# LED_005.net
KiCad netlist of a schematic drawn in EAGLE
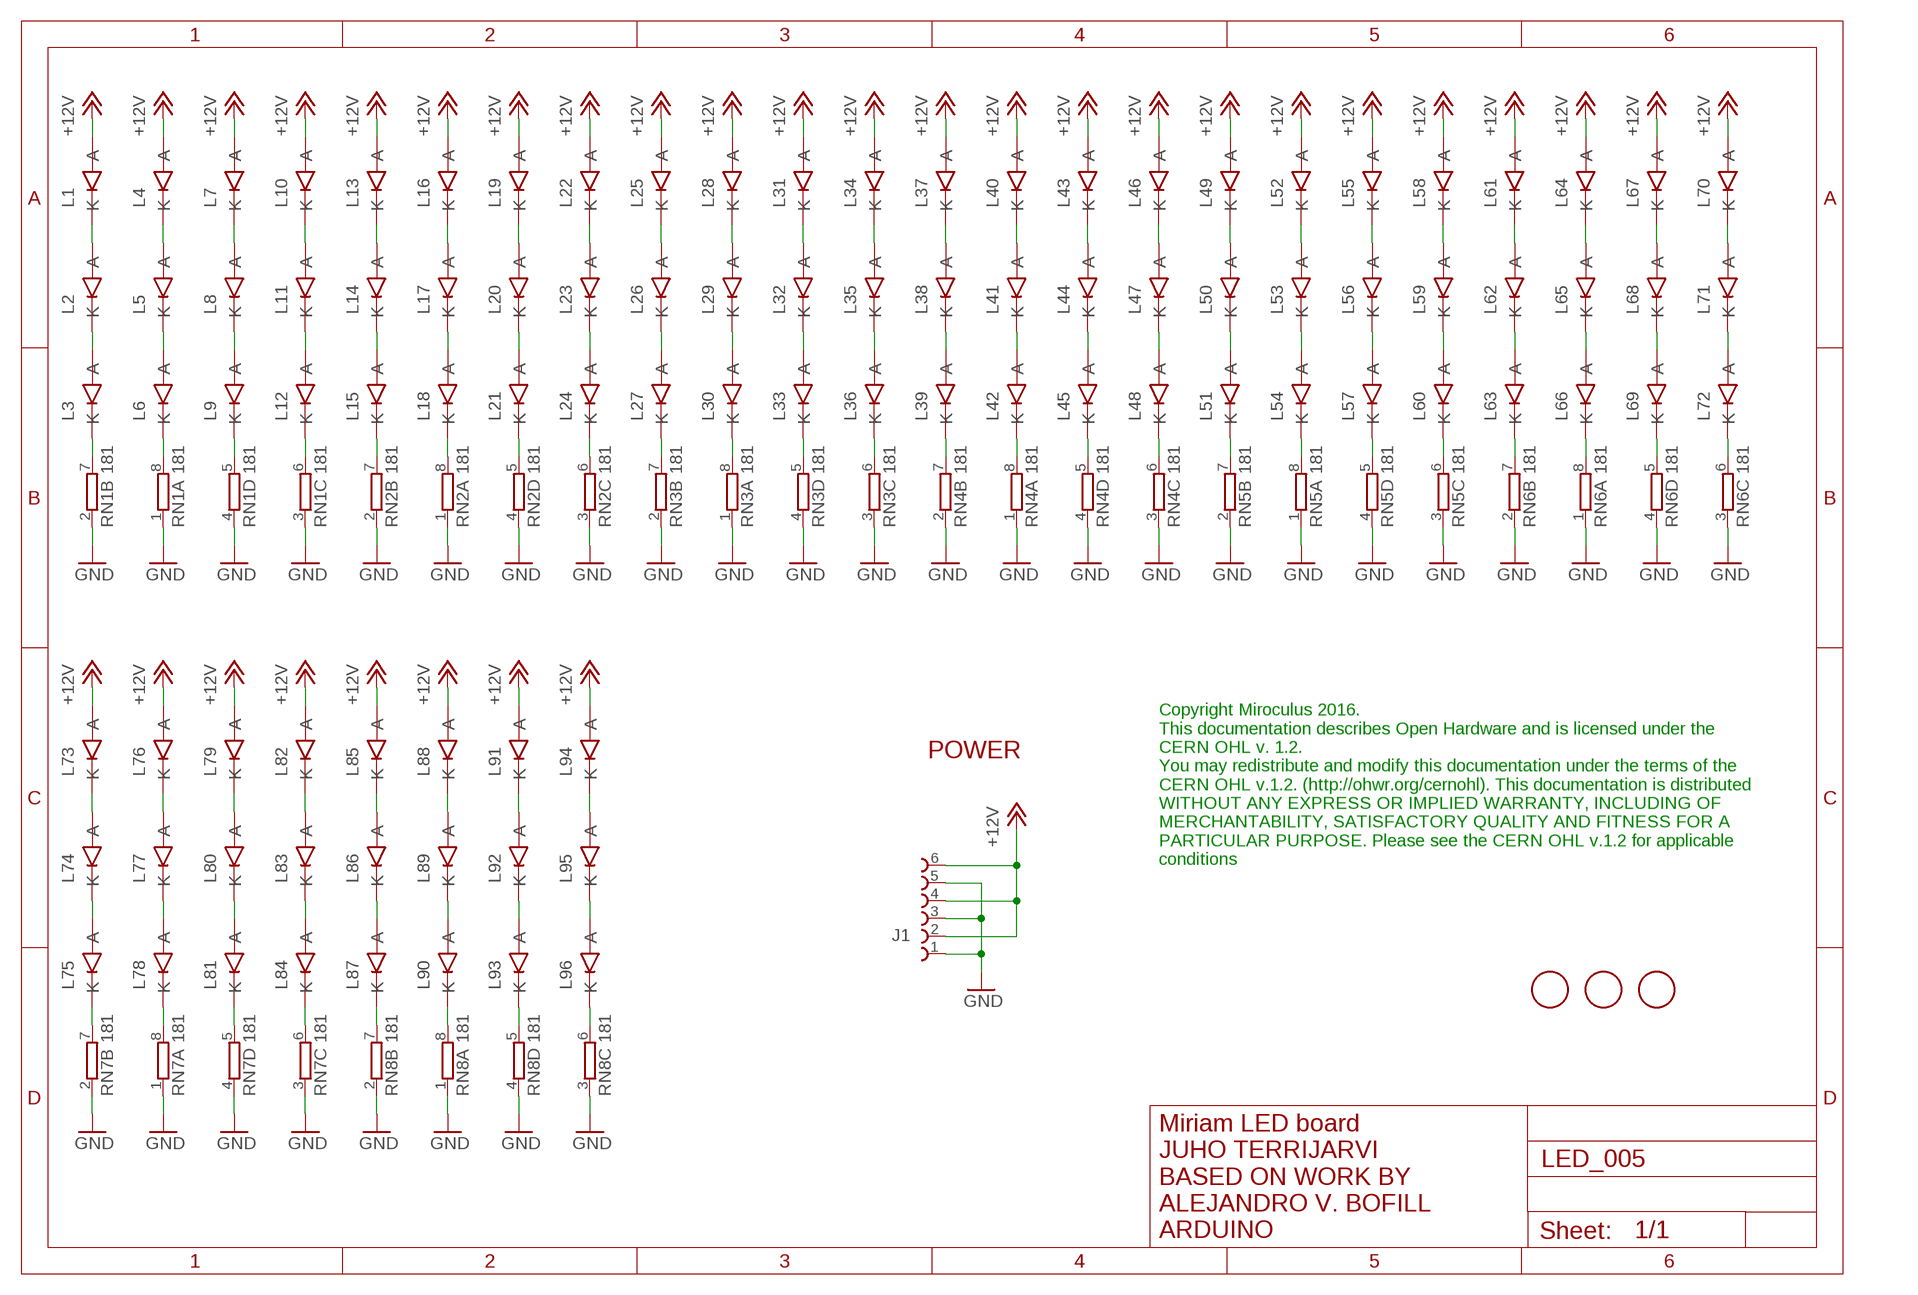
[diagram p0: schematic, sheet 1]

(export (version "E")
  (design (tool "Eeschema 10.0.6"))
  (components
    (comp (ref "FD1")
      (value "FIDUCIALMOUNT")
      (footprint "eagle-import:FIDUCIA-MOUNT")
      (libsource (lib "eagle-import") (part "FIDUCIALMOUNT"))
    )
    (comp (ref "FD2")
      (value "FIDUCIALMOUNT")
      (footprint "eagle-import:FIDUCIA-MOUNT")
      (libsource (lib "eagle-import") (part "FIDUCIALMOUNT"))
    )
    (comp (ref "FD3")
      (value "FIDUCIALMOUNT")
      (footprint "eagle-import:FIDUCIA-MOUNT")
      (libsource (lib "eagle-import") (part "FIDUCIALMOUNT"))
    )
    (comp (ref "J1")
      (value "68710614522")
      (footprint "eagle-import:68710614522")
      (libsource (lib "eagle-import") (part "68710614522"))
    )
    (comp (ref "L1")
      (value "KA-2810AQBS-G")
      (footprint "eagle-import:LED_0.2")
      (libsource (lib "eagle-import") (part "LED_0.2"))
    )
    (comp (ref "L2")
      (value "KA-2810AQBS-G")
      (footprint "eagle-import:LED_0.2")
      (libsource (lib "eagle-import") (part "LED_0.2"))
    )
    (comp (ref "L3")
      (value "KA-2810AQBS-G")
      (footprint "eagle-import:LED_0.2")
      (libsource (lib "eagle-import") (part "LED_0.2"))
    )
    (comp (ref "L4")
      (value "KA-2810AQBS-G")
      (footprint "eagle-import:LED_0.2")
      (libsource (lib "eagle-import") (part "LED_0.2"))
    )
    (comp (ref "L5")
      (value "KA-2810AQBS-G")
      (footprint "eagle-import:LED_0.2")
      (libsource (lib "eagle-import") (part "LED_0.2"))
    )
    (comp (ref "L6")
      (value "KA-2810AQBS-G")
      (footprint "eagle-import:LED_0.2")
      (libsource (lib "eagle-import") (part "LED_0.2"))
    )
    (comp (ref "L7")
      (value "KA-2810AQBS-G")
      (footprint "eagle-import:LED_0.2")
      (libsource (lib "eagle-import") (part "LED_0.2"))
    )
    (comp (ref "L8")
      (value "KA-2810AQBS-G")
      (footprint "eagle-import:LED_0.2")
      (libsource (lib "eagle-import") (part "LED_0.2"))
    )
    (comp (ref "L9")
      (value "KA-2810AQBS-G")
      (footprint "eagle-import:LED_0.2")
      (libsource (lib "eagle-import") (part "LED_0.2"))
    )
    (comp (ref "L10")
      (value "KA-2810AQBS-G")
      (footprint "eagle-import:LED_0.2")
      (libsource (lib "eagle-import") (part "LED_0.2"))
    )
    (comp (ref "L11")
      (value "KA-2810AQBS-G")
      (footprint "eagle-import:LED_0.2")
      (libsource (lib "eagle-import") (part "LED_0.2"))
    )
    (comp (ref "L12")
      (value "KA-2810AQBS-G")
      (footprint "eagle-import:LED_0.2")
      (libsource (lib "eagle-import") (part "LED_0.2"))
    )
    (comp (ref "L13")
      (value "KA-2810AQBS-G")
      (footprint "eagle-import:LED_0.2")
      (libsource (lib "eagle-import") (part "LED_0.2"))
    )
    (comp (ref "L14")
      (value "KA-2810AQBS-G")
      (footprint "eagle-import:LED_0.2")
      (libsource (lib "eagle-import") (part "LED_0.2"))
    )
    (comp (ref "L15")
      (value "KA-2810AQBS-G")
      (footprint "eagle-import:LED_0.2")
      (libsource (lib "eagle-import") (part "LED_0.2"))
    )
    (comp (ref "L16")
      (value "KA-2810AQBS-G")
      (footprint "eagle-import:LED_0.2")
      (libsource (lib "eagle-import") (part "LED_0.2"))
    )
    (comp (ref "L17")
      (value "KA-2810AQBS-G")
      (footprint "eagle-import:LED_0.2")
      (libsource (lib "eagle-import") (part "LED_0.2"))
    )
    (comp (ref "L18")
      (value "KA-2810AQBS-G")
      (footprint "eagle-import:LED_0.2")
      (libsource (lib "eagle-import") (part "LED_0.2"))
    )
    (comp (ref "L19")
      (value "KA-2810AQBS-G")
      (footprint "eagle-import:LED_0.2")
      (libsource (lib "eagle-import") (part "LED_0.2"))
    )
    (comp (ref "L20")
      (value "KA-2810AQBS-G")
      (footprint "eagle-import:LED_0.2")
      (libsource (lib "eagle-import") (part "LED_0.2"))
    )
    (comp (ref "L21")
      (value "KA-2810AQBS-G")
      (footprint "eagle-import:LED_0.2")
      (libsource (lib "eagle-import") (part "LED_0.2"))
    )
    (comp (ref "L22")
      (value "KA-2810AQBS-G")
      (footprint "eagle-import:LED_0.2")
      (libsource (lib "eagle-import") (part "LED_0.2"))
    )
    (comp (ref "L23")
      (value "KA-2810AQBS-G")
      (footprint "eagle-import:LED_0.2")
      (libsource (lib "eagle-import") (part "LED_0.2"))
    )
    (comp (ref "L24")
      (value "KA-2810AQBS-G")
      (footprint "eagle-import:LED_0.2")
      (libsource (lib "eagle-import") (part "LED_0.2"))
    )
    (comp (ref "L25")
      (value "KA-2810AQBS-G")
      (footprint "eagle-import:LED_0.2")
      (libsource (lib "eagle-import") (part "LED_0.2"))
    )
    (comp (ref "L26")
      (value "KA-2810AQBS-G")
      (footprint "eagle-import:LED_0.2")
      (libsource (lib "eagle-import") (part "LED_0.2"))
    )
    (comp (ref "L27")
      (value "KA-2810AQBS-G")
      (footprint "eagle-import:LED_0.2")
      (libsource (lib "eagle-import") (part "LED_0.2"))
    )
    (comp (ref "L28")
      (value "KA-2810AQBS-G")
      (footprint "eagle-import:LED_0.2")
      (libsource (lib "eagle-import") (part "LED_0.2"))
    )
    (comp (ref "L29")
      (value "KA-2810AQBS-G")
      (footprint "eagle-import:LED_0.2")
      (libsource (lib "eagle-import") (part "LED_0.2"))
    )
    (comp (ref "L30")
      (value "KA-2810AQBS-G")
      (footprint "eagle-import:LED_0.2")
      (libsource (lib "eagle-import") (part "LED_0.2"))
    )
    (comp (ref "L31")
      (value "KA-2810AQBS-G")
      (footprint "eagle-import:LED_0.2")
      (libsource (lib "eagle-import") (part "LED_0.2"))
    )
    (comp (ref "L32")
      (value "KA-2810AQBS-G")
      (footprint "eagle-import:LED_0.2")
      (libsource (lib "eagle-import") (part "LED_0.2"))
    )
    (comp (ref "L33")
      (value "KA-2810AQBS-G")
      (footprint "eagle-import:LED_0.2")
      (libsource (lib "eagle-import") (part "LED_0.2"))
    )
    (comp (ref "L34")
      (value "KA-2810AQBS-G")
      (footprint "eagle-import:LED_0.2")
      (libsource (lib "eagle-import") (part "LED_0.2"))
    )
    (comp (ref "L35")
      (value "KA-2810AQBS-G")
      (footprint "eagle-import:LED_0.2")
      (libsource (lib "eagle-import") (part "LED_0.2"))
    )
    (comp (ref "L36")
      (value "KA-2810AQBS-G")
      (footprint "eagle-import:LED_0.2")
      (libsource (lib "eagle-import") (part "LED_0.2"))
    )
    (comp (ref "L37")
      (value "KA-2810AQBS-G")
      (footprint "eagle-import:LED_0.2")
      (libsource (lib "eagle-import") (part "LED_0.2"))
    )
    (comp (ref "L38")
      (value "KA-2810AQBS-G")
      (footprint "eagle-import:LED_0.2")
      (libsource (lib "eagle-import") (part "LED_0.2"))
    )
    (comp (ref "L39")
      (value "KA-2810AQBS-G")
      (footprint "eagle-import:LED_0.2")
      (libsource (lib "eagle-import") (part "LED_0.2"))
    )
    (comp (ref "L40")
      (value "KA-2810AQBS-G")
      (footprint "eagle-import:LED_0.2")
      (libsource (lib "eagle-import") (part "LED_0.2"))
    )
    (comp (ref "L41")
      (value "KA-2810AQBS-G")
      (footprint "eagle-import:LED_0.2")
      (libsource (lib "eagle-import") (part "LED_0.2"))
    )
    (comp (ref "L42")
      (value "KA-2810AQBS-G")
      (footprint "eagle-import:LED_0.2")
      (libsource (lib "eagle-import") (part "LED_0.2"))
    )
    (comp (ref "L43")
      (value "KA-2810AQBS-G")
      (footprint "eagle-import:LED_0.2")
      (libsource (lib "eagle-import") (part "LED_0.2"))
    )
    (comp (ref "L44")
      (value "KA-2810AQBS-G")
      (footprint "eagle-import:LED_0.2")
      (libsource (lib "eagle-import") (part "LED_0.2"))
    )
    (comp (ref "L45")
      (value "KA-2810AQBS-G")
      (footprint "eagle-import:LED_0.2")
      (libsource (lib "eagle-import") (part "LED_0.2"))
    )
    (comp (ref "L46")
      (value "KA-2810AQBS-G")
      (footprint "eagle-import:LED_0.2")
      (libsource (lib "eagle-import") (part "LED_0.2"))
    )
    (comp (ref "L47")
      (value "KA-2810AQBS-G")
      (footprint "eagle-import:LED_0.2")
      (libsource (lib "eagle-import") (part "LED_0.2"))
    )
    (comp (ref "L48")
      (value "KA-2810AQBS-G")
      (footprint "eagle-import:LED_0.2")
      (libsource (lib "eagle-import") (part "LED_0.2"))
    )
    (comp (ref "L49")
      (value "KA-2810AQBS-G")
      (footprint "eagle-import:LED_0.2")
      (libsource (lib "eagle-import") (part "LED_0.2"))
    )
    (comp (ref "L50")
      (value "KA-2810AQBS-G")
      (footprint "eagle-import:LED_0.2")
      (libsource (lib "eagle-import") (part "LED_0.2"))
    )
    (comp (ref "L51")
      (value "KA-2810AQBS-G")
      (footprint "eagle-import:LED_0.2")
      (libsource (lib "eagle-import") (part "LED_0.2"))
    )
    (comp (ref "L52")
      (value "KA-2810AQBS-G")
      (footprint "eagle-import:LED_0.2")
      (libsource (lib "eagle-import") (part "LED_0.2"))
    )
    (comp (ref "L53")
      (value "KA-2810AQBS-G")
      (footprint "eagle-import:LED_0.2")
      (libsource (lib "eagle-import") (part "LED_0.2"))
    )
    (comp (ref "L54")
      (value "KA-2810AQBS-G")
      (footprint "eagle-import:LED_0.2")
      (libsource (lib "eagle-import") (part "LED_0.2"))
    )
    (comp (ref "L55")
      (value "KA-2810AQBS-G")
      (footprint "eagle-import:LED_0.2")
      (libsource (lib "eagle-import") (part "LED_0.2"))
    )
    (comp (ref "L56")
      (value "KA-2810AQBS-G")
      (footprint "eagle-import:LED_0.2")
      (libsource (lib "eagle-import") (part "LED_0.2"))
    )
    (comp (ref "L57")
      (value "KA-2810AQBS-G")
      (footprint "eagle-import:LED_0.2")
      (libsource (lib "eagle-import") (part "LED_0.2"))
    )
    (comp (ref "L58")
      (value "KA-2810AQBS-G")
      (footprint "eagle-import:LED_0.2")
      (libsource (lib "eagle-import") (part "LED_0.2"))
    )
    (comp (ref "L59")
      (value "KA-2810AQBS-G")
      (footprint "eagle-import:LED_0.2")
      (libsource (lib "eagle-import") (part "LED_0.2"))
    )
    (comp (ref "L60")
      (value "KA-2810AQBS-G")
      (footprint "eagle-import:LED_0.2")
      (libsource (lib "eagle-import") (part "LED_0.2"))
    )
    (comp (ref "L61")
      (value "KA-2810AQBS-G")
      (footprint "eagle-import:LED_0.2")
      (libsource (lib "eagle-import") (part "LED_0.2"))
    )
    (comp (ref "L62")
      (value "KA-2810AQBS-G")
      (footprint "eagle-import:LED_0.2")
      (libsource (lib "eagle-import") (part "LED_0.2"))
    )
    (comp (ref "L63")
      (value "KA-2810AQBS-G")
      (footprint "eagle-import:LED_0.2")
      (libsource (lib "eagle-import") (part "LED_0.2"))
    )
    (comp (ref "L64")
      (value "KA-2810AQBS-G")
      (footprint "eagle-import:LED_0.2")
      (libsource (lib "eagle-import") (part "LED_0.2"))
    )
    (comp (ref "L65")
      (value "KA-2810AQBS-G")
      (footprint "eagle-import:LED_0.2")
      (libsource (lib "eagle-import") (part "LED_0.2"))
    )
    (comp (ref "L66")
      (value "KA-2810AQBS-G")
      (footprint "eagle-import:LED_0.2")
      (libsource (lib "eagle-import") (part "LED_0.2"))
    )
    (comp (ref "L67")
      (value "KA-2810AQBS-G")
      (footprint "eagle-import:LED_0.2")
      (libsource (lib "eagle-import") (part "LED_0.2"))
    )
    (comp (ref "L68")
      (value "KA-2810AQBS-G")
      (footprint "eagle-import:LED_0.2")
      (libsource (lib "eagle-import") (part "LED_0.2"))
    )
    (comp (ref "L69")
      (value "KA-2810AQBS-G")
      (footprint "eagle-import:LED_0.2")
      (libsource (lib "eagle-import") (part "LED_0.2"))
    )
    (comp (ref "L70")
      (value "KA-2810AQBS-G")
      (footprint "eagle-import:LED_0.2")
      (libsource (lib "eagle-import") (part "LED_0.2"))
    )
    (comp (ref "L71")
      (value "KA-2810AQBS-G")
      (footprint "eagle-import:LED_0.2")
      (libsource (lib "eagle-import") (part "LED_0.2"))
    )
    (comp (ref "L72")
      (value "KA-2810AQBS-G")
      (footprint "eagle-import:LED_0.2")
      (libsource (lib "eagle-import") (part "LED_0.2"))
    )
    (comp (ref "L73")
      (value "KA-2810AQBS-G")
      (footprint "eagle-import:LED_0.2")
      (libsource (lib "eagle-import") (part "LED_0.2"))
    )
    (comp (ref "L74")
      (value "KA-2810AQBS-G")
      (footprint "eagle-import:LED_0.2")
      (libsource (lib "eagle-import") (part "LED_0.2"))
    )
    (comp (ref "L75")
      (value "KA-2810AQBS-G")
      (footprint "eagle-import:LED_0.2")
      (libsource (lib "eagle-import") (part "LED_0.2"))
    )
    (comp (ref "L76")
      (value "KA-2810AQBS-G")
      (footprint "eagle-import:LED_0.2")
      (libsource (lib "eagle-import") (part "LED_0.2"))
    )
    (comp (ref "L77")
      (value "KA-2810AQBS-G")
      (footprint "eagle-import:LED_0.2")
      (libsource (lib "eagle-import") (part "LED_0.2"))
    )
    (comp (ref "L78")
      (value "KA-2810AQBS-G")
      (footprint "eagle-import:LED_0.2")
      (libsource (lib "eagle-import") (part "LED_0.2"))
    )
    (comp (ref "L79")
      (value "KA-2810AQBS-G")
      (footprint "eagle-import:LED_0.2")
      (libsource (lib "eagle-import") (part "LED_0.2"))
    )
    (comp (ref "L80")
      (value "KA-2810AQBS-G")
      (footprint "eagle-import:LED_0.2")
      (libsource (lib "eagle-import") (part "LED_0.2"))
    )
    (comp (ref "L81")
      (value "KA-2810AQBS-G")
      (footprint "eagle-import:LED_0.2")
      (libsource (lib "eagle-import") (part "LED_0.2"))
    )
    (comp (ref "L82")
      (value "KA-2810AQBS-G")
      (footprint "eagle-import:LED_0.2")
      (libsource (lib "eagle-import") (part "LED_0.2"))
    )
    (comp (ref "L83")
      (value "KA-2810AQBS-G")
      (footprint "eagle-import:LED_0.2")
      (libsource (lib "eagle-import") (part "LED_0.2"))
    )
    (comp (ref "L84")
      (value "KA-2810AQBS-G")
      (footprint "eagle-import:LED_0.2")
      (libsource (lib "eagle-import") (part "LED_0.2"))
    )
    (comp (ref "L85")
      (value "KA-2810AQBS-G")
      (footprint "eagle-import:LED_0.2")
      (libsource (lib "eagle-import") (part "LED_0.2"))
    )
    (comp (ref "L86")
      (value "KA-2810AQBS-G")
      (footprint "eagle-import:LED_0.2")
      (libsource (lib "eagle-import") (part "LED_0.2"))
    )
    (comp (ref "L87")
      (value "KA-2810AQBS-G")
      (footprint "eagle-import:LED_0.2")
      (libsource (lib "eagle-import") (part "LED_0.2"))
    )
    (comp (ref "L88")
      (value "KA-2810AQBS-G")
      (footprint "eagle-import:LED_0.2")
      (libsource (lib "eagle-import") (part "LED_0.2"))
    )
    (comp (ref "L89")
      (value "KA-2810AQBS-G")
      (footprint "eagle-import:LED_0.2")
      (libsource (lib "eagle-import") (part "LED_0.2"))
    )
    (comp (ref "L90")
      (value "KA-2810AQBS-G")
      (footprint "eagle-import:LED_0.2")
      (libsource (lib "eagle-import") (part "LED_0.2"))
    )
    (comp (ref "L91")
      (value "KA-2810AQBS-G")
      (footprint "eagle-import:LED_0.2")
      (libsource (lib "eagle-import") (part "LED_0.2"))
    )
    (comp (ref "L92")
      (value "KA-2810AQBS-G")
      (footprint "eagle-import:LED_0.2")
      (libsource (lib "eagle-import") (part "LED_0.2"))
    )
    (comp (ref "L93")
      (value "KA-2810AQBS-G")
      (footprint "eagle-import:LED_0.2")
      (libsource (lib "eagle-import") (part "LED_0.2"))
    )
    (comp (ref "L94")
      (value "KA-2810AQBS-G")
      (footprint "eagle-import:LED_0.2")
      (libsource (lib "eagle-import") (part "LED_0.2"))
    )
    (comp (ref "L95")
      (value "KA-2810AQBS-G")
      (footprint "eagle-import:LED_0.2")
      (libsource (lib "eagle-import") (part "LED_0.2"))
    )
    (comp (ref "L96")
      (value "KA-2810AQBS-G")
      (footprint "eagle-import:LED_0.2")
      (libsource (lib "eagle-import") (part "LED_0.2"))
    )
    (comp (ref "RN1")
      (value "181")
      (footprint "eagle-import:CAY16")
      (libsource (lib "eagle-import") (part "4R-NCAY16"))
    )
    (comp (ref "RN2")
      (value "181")
      (footprint "eagle-import:CAY16")
      (libsource (lib "eagle-import") (part "4R-NCAY16"))
    )
    (comp (ref "RN3")
      (value "181")
      (footprint "eagle-import:CAY16")
      (libsource (lib "eagle-import") (part "4R-NCAY16"))
    )
    (comp (ref "RN4")
      (value "181")
      (footprint "eagle-import:CAY16")
      (libsource (lib "eagle-import") (part "4R-NCAY16"))
    )
    (comp (ref "RN5")
      (value "181")
      (footprint "eagle-import:CAY16")
      (libsource (lib "eagle-import") (part "4R-NCAY16"))
    )
    (comp (ref "RN6")
      (value "181")
      (footprint "eagle-import:CAY16")
      (libsource (lib "eagle-import") (part "4R-NCAY16"))
    )
    (comp (ref "RN7")
      (value "181")
      (footprint "eagle-import:CAY16")
      (libsource (lib "eagle-import") (part "4R-NCAY16"))
    )
    (comp (ref "RN8")
      (value "181")
      (footprint "eagle-import:CAY16")
      (libsource (lib "eagle-import") (part "4R-NCAY16"))
    )
  )
  (nets
    (net (code "1") (name "+12V") (class "Default")
      (node (ref "J1") (pin "2") (pinfunction "2_2") (pintype "passive"))
      (node (ref "J1") (pin "4") (pinfunction "4_4") (pintype "passive"))
      (node (ref "J1") (pin "6") (pinfunction "6_6") (pintype "passive"))
      (node (ref "L1") (pin "2") (pinfunction "A_2") (pintype "input"))
      (node (ref "L10") (pin "2") (pinfunction "A_2") (pintype "input"))
      (node (ref "L13") (pin "2") (pinfunction "A_2") (pintype "input"))
      (node (ref "L16") (pin "2") (pinfunction "A_2") (pintype "input"))
      (node (ref "L19") (pin "2") (pinfunction "A_2") (pintype "input"))
      (node (ref "L22") (pin "2") (pinfunction "A_2") (pintype "input"))
      (node (ref "L25") (pin "2") (pinfunction "A_2") (pintype "input"))
      (node (ref "L28") (pin "2") (pinfunction "A_2") (pintype "input"))
      (node (ref "L31") (pin "2") (pinfunction "A_2") (pintype "input"))
      (node (ref "L34") (pin "2") (pinfunction "A_2") (pintype "input"))
      (node (ref "L37") (pin "2") (pinfunction "A_2") (pintype "input"))
      (node (ref "L4") (pin "2") (pinfunction "A_2") (pintype "input"))
      (node (ref "L40") (pin "2") (pinfunction "A_2") (pintype "input"))
      (node (ref "L43") (pin "2") (pinfunction "A_2") (pintype "input"))
      (node (ref "L46") (pin "2") (pinfunction "A_2") (pintype "input"))
      (node (ref "L49") (pin "2") (pinfunction "A_2") (pintype "input"))
      (node (ref "L52") (pin "2") (pinfunction "A_2") (pintype "input"))
      (node (ref "L55") (pin "2") (pinfunction "A_2") (pintype "input"))
      (node (ref "L58") (pin "2") (pinfunction "A_2") (pintype "input"))
      (node (ref "L61") (pin "2") (pinfunction "A_2") (pintype "input"))
      (node (ref "L64") (pin "2") (pinfunction "A_2") (pintype "input"))
      (node (ref "L67") (pin "2") (pinfunction "A_2") (pintype "input"))
      (node (ref "L7") (pin "2") (pinfunction "A_2") (pintype "input"))
      (node (ref "L70") (pin "2") (pinfunction "A_2") (pintype "input"))
      (node (ref "L73") (pin "2") (pinfunction "A_2") (pintype "input"))
      (node (ref "L76") (pin "2") (pinfunction "A_2") (pintype "input"))
      (node (ref "L79") (pin "2") (pinfunction "A_2") (pintype "input"))
      (node (ref "L82") (pin "2") (pinfunction "A_2") (pintype "input"))
      (node (ref "L85") (pin "2") (pinfunction "A_2") (pintype "input"))
      (node (ref "L88") (pin "2") (pinfunction "A_2") (pintype "input"))
      (node (ref "L91") (pin "2") (pinfunction "A_2") (pintype "input"))
      (node (ref "L94") (pin "2") (pinfunction "A_2") (pintype "input"))
    )
    (net (code "2") (name "GND") (class "Default")
      (node (ref "J1") (pin "1") (pinfunction "1_1") (pintype "passive"))
      (node (ref "J1") (pin "3") (pinfunction "3_3") (pintype "passive"))
      (node (ref "J1") (pin "5") (pinfunction "5_5") (pintype "passive"))
      (node (ref "RN1") (pin "1") (pinfunction "1_1") (pintype "passive"))
      (node (ref "RN1") (pin "2") (pinfunction "1_2") (pintype "passive"))
      (node (ref "RN1") (pin "3") (pinfunction "1_3") (pintype "passive"))
      (node (ref "RN1") (pin "4") (pinfunction "1_4") (pintype "passive"))
      (node (ref "RN2") (pin "1") (pinfunction "1_1") (pintype "passive"))
      (node (ref "RN2") (pin "2") (pinfunction "1_2") (pintype "passive"))
      (node (ref "RN2") (pin "3") (pinfunction "1_3") (pintype "passive"))
      (node (ref "RN2") (pin "4") (pinfunction "1_4") (pintype "passive"))
      (node (ref "RN3") (pin "1") (pinfunction "1_1") (pintype "passive"))
      (node (ref "RN3") (pin "2") (pinfunction "1_2") (pintype "passive"))
      (node (ref "RN3") (pin "3") (pinfunction "1_3") (pintype "passive"))
      (node (ref "RN3") (pin "4") (pinfunction "1_4") (pintype "passive"))
      (node (ref "RN4") (pin "1") (pinfunction "1_1") (pintype "passive"))
      (node (ref "RN4") (pin "2") (pinfunction "1_2") (pintype "passive"))
      (node (ref "RN4") (pin "3") (pinfunction "1_3") (pintype "passive"))
      (node (ref "RN4") (pin "4") (pinfunction "1_4") (pintype "passive"))
      (node (ref "RN5") (pin "1") (pinfunction "1_1") (pintype "passive"))
      (node (ref "RN5") (pin "2") (pinfunction "1_2") (pintype "passive"))
      (node (ref "RN5") (pin "3") (pinfunction "1_3") (pintype "passive"))
      (node (ref "RN5") (pin "4") (pinfunction "1_4") (pintype "passive"))
      (node (ref "RN6") (pin "1") (pinfunction "1_1") (pintype "passive"))
      (node (ref "RN6") (pin "2") (pinfunction "1_2") (pintype "passive"))
      (node (ref "RN6") (pin "3") (pinfunction "1_3") (pintype "passive"))
      (node (ref "RN6") (pin "4") (pinfunction "1_4") (pintype "passive"))
      (node (ref "RN7") (pin "1") (pinfunction "1_1") (pintype "passive"))
      (node (ref "RN7") (pin "2") (pinfunction "1_2") (pintype "passive"))
      (node (ref "RN7") (pin "3") (pinfunction "1_3") (pintype "passive"))
      (node (ref "RN7") (pin "4") (pinfunction "1_4") (pintype "passive"))
      (node (ref "RN8") (pin "1") (pinfunction "1_1") (pintype "passive"))
      (node (ref "RN8") (pin "2") (pinfunction "1_2") (pintype "passive"))
      (node (ref "RN8") (pin "3") (pinfunction "1_3") (pintype "passive"))
      (node (ref "RN8") (pin "4") (pinfunction "1_4") (pintype "passive"))
    )
    (net (code "3") (name "Net-(L1-K)") (class "Default")
      (node (ref "L1") (pin "1") (pinfunction "K_1") (pintype "output"))
      (node (ref "L2") (pin "2") (pinfunction "A_2") (pintype "input"))
    )
    (net (code "4") (name "Net-(L2-K)") (class "Default")
      (node (ref "L2") (pin "1") (pinfunction "K_1") (pintype "output"))
      (node (ref "L3") (pin "2") (pinfunction "A_2") (pintype "input"))
    )
    (net (code "5") (name "Net-(L3-K)") (class "Default")
      (node (ref "L3") (pin "1") (pinfunction "K_1") (pintype "output"))
      (node (ref "RN1") (pin "7") (pinfunction "2_7") (pintype "passive"))
    )
    (net (code "6") (name "Net-(L4-K)") (class "Default")
      (node (ref "L4") (pin "1") (pinfunction "K_1") (pintype "output"))
      (node (ref "L5") (pin "2") (pinfunction "A_2") (pintype "input"))
    )
    (net (code "7") (name "Net-(L5-K)") (class "Default")
      (node (ref "L5") (pin "1") (pinfunction "K_1") (pintype "output"))
      (node (ref "L6") (pin "2") (pinfunction "A_2") (pintype "input"))
    )
    (net (code "8") (name "Net-(L6-K)") (class "Default")
      (node (ref "L6") (pin "1") (pinfunction "K_1") (pintype "output"))
      (node (ref "RN1") (pin "8") (pinfunction "2_8") (pintype "passive"))
    )
    (net (code "9") (name "Net-(L7-K)") (class "Default")
      (node (ref "L7") (pin "1") (pinfunction "K_1") (pintype "output"))
      (node (ref "L8") (pin "2") (pinfunction "A_2") (pintype "input"))
    )
    (net (code "10") (name "Net-(L8-K)") (class "Default")
      (node (ref "L8") (pin "1") (pinfunction "K_1") (pintype "output"))
      (node (ref "L9") (pin "2") (pinfunction "A_2") (pintype "input"))
    )
    (net (code "11") (name "Net-(L9-K)") (class "Default")
      (node (ref "L9") (pin "1") (pinfunction "K_1") (pintype "output"))
      (node (ref "RN1") (pin "5") (pinfunction "2_5") (pintype "passive"))
    )
    (net (code "12") (name "Net-(L10-K)") (class "Default")
      (node (ref "L10") (pin "1") (pinfunction "K_1") (pintype "output"))
      (node (ref "L11") (pin "2") (pinfunction "A_2") (pintype "input"))
    )
    (net (code "13") (name "Net-(L11-K)") (class "Default")
      (node (ref "L11") (pin "1") (pinfunction "K_1") (pintype "output"))
      (node (ref "L12") (pin "2") (pinfunction "A_2") (pintype "input"))
    )
    (net (code "14") (name "Net-(L12-K)") (class "Default")
      (node (ref "L12") (pin "1") (pinfunction "K_1") (pintype "output"))
      (node (ref "RN1") (pin "6") (pinfunction "2_6") (pintype "passive"))
    )
    (net (code "15") (name "Net-(L13-K)") (class "Default")
      (node (ref "L13") (pin "1") (pinfunction "K_1") (pintype "output"))
      (node (ref "L14") (pin "2") (pinfunction "A_2") (pintype "input"))
    )
    (net (code "16") (name "Net-(L14-K)") (class "Default")
      (node (ref "L14") (pin "1") (pinfunction "K_1") (pintype "output"))
      (node (ref "L15") (pin "2") (pinfunction "A_2") (pintype "input"))
    )
    (net (code "17") (name "Net-(L15-K)") (class "Default")
      (node (ref "L15") (pin "1") (pinfunction "K_1") (pintype "output"))
      (node (ref "RN2") (pin "7") (pinfunction "2_7") (pintype "passive"))
    )
    (net (code "18") (name "Net-(L16-K)") (class "Default")
      (node (ref "L16") (pin "1") (pinfunction "K_1") (pintype "output"))
      (node (ref "L17") (pin "2") (pinfunction "A_2") (pintype "input"))
    )
    (net (code "19") (name "Net-(L17-K)") (class "Default")
      (node (ref "L17") (pin "1") (pinfunction "K_1") (pintype "output"))
      (node (ref "L18") (pin "2") (pinfunction "A_2") (pintype "input"))
    )
    (net (code "20") (name "Net-(L18-K)") (class "Default")
      (node (ref "L18") (pin "1") (pinfunction "K_1") (pintype "output"))
      (node (ref "RN2") (pin "8") (pinfunction "2_8") (pintype "passive"))
    )
    (net (code "21") (name "Net-(L19-K)") (class "Default")
      (node (ref "L19") (pin "1") (pinfunction "K_1") (pintype "output"))
      (node (ref "L20") (pin "2") (pinfunction "A_2") (pintype "input"))
    )
    (net (code "22") (name "Net-(L20-K)") (class "Default")
      (node (ref "L20") (pin "1") (pinfunction "K_1") (pintype "output"))
      (node (ref "L21") (pin "2") (pinfunction "A_2") (pintype "input"))
    )
    (net (code "23") (name "Net-(L21-K)") (class "Default")
      (node (ref "L21") (pin "1") (pinfunction "K_1") (pintype "output"))
      (node (ref "RN2") (pin "5") (pinfunction "2_5") (pintype "passive"))
    )
    (net (code "24") (name "Net-(L22-K)") (class "Default")
      (node (ref "L22") (pin "1") (pinfunction "K_1") (pintype "output"))
      (node (ref "L23") (pin "2") (pinfunction "A_2") (pintype "input"))
    )
    (net (code "25") (name "Net-(L23-K)") (class "Default")
      (node (ref "L23") (pin "1") (pinfunction "K_1") (pintype "output"))
      (node (ref "L24") (pin "2") (pinfunction "A_2") (pintype "input"))
    )
    (net (code "26") (name "Net-(L24-K)") (class "Default")
      (node (ref "L24") (pin "1") (pinfunction "K_1") (pintype "output"))
      (node (ref "RN2") (pin "6") (pinfunction "2_6") (pintype "passive"))
    )
    (net (code "27") (name "Net-(L25-K)") (class "Default")
      (node (ref "L25") (pin "1") (pinfunction "K_1") (pintype "output"))
      (node (ref "L26") (pin "2") (pinfunction "A_2") (pintype "input"))
    )
    (net (code "28") (name "Net-(L26-K)") (class "Default")
      (node (ref "L26") (pin "1") (pinfunction "K_1") (pintype "output"))
      (node (ref "L27") (pin "2") (pinfunction "A_2") (pintype "input"))
    )
    (net (code "29") (name "Net-(L27-K)") (class "Default")
      (node (ref "L27") (pin "1") (pinfunction "K_1") (pintype "output"))
      (node (ref "RN3") (pin "7") (pinfunction "2_7") (pintype "passive"))
    )
    (net (code "30") (name "Net-(L28-K)") (class "Default")
      (node (ref "L28") (pin "1") (pinfunction "K_1") (pintype "output"))
      (node (ref "L29") (pin "2") (pinfunction "A_2") (pintype "input"))
    )
    (net (code "31") (name "Net-(L29-K)") (class "Default")
      (node (ref "L29") (pin "1") (pinfunction "K_1") (pintype "output"))
      (node (ref "L30") (pin "2") (pinfunction "A_2") (pintype "input"))
    )
    (net (code "32") (name "Net-(L30-K)") (class "Default")
      (node (ref "L30") (pin "1") (pinfunction "K_1") (pintype "output"))
      (node (ref "RN3") (pin "8") (pinfunction "2_8") (pintype "passive"))
    )
    (net (code "33") (name "Net-(L31-K)") (class "Default")
      (node (ref "L31") (pin "1") (pinfunction "K_1") (pintype "output"))
      (node (ref "L32") (pin "2") (pinfunction "A_2") (pintype "input"))
    )
    (net (code "34") (name "Net-(L32-K)") (class "Default")
      (node (ref "L32") (pin "1") (pinfunction "K_1") (pintype "output"))
      (node (ref "L33") (pin "2") (pinfunction "A_2") (pintype "input"))
    )
    (net (code "35") (name "Net-(L33-K)") (class "Default")
      (node (ref "L33") (pin "1") (pinfunction "K_1") (pintype "output"))
      (node (ref "RN3") (pin "5") (pinfunction "2_5") (pintype "passive"))
    )
    (net (code "36") (name "Net-(L34-K)") (class "Default")
      (node (ref "L34") (pin "1") (pinfunction "K_1") (pintype "output"))
      (node (ref "L35") (pin "2") (pinfunction "A_2") (pintype "input"))
    )
    (net (code "37") (name "Net-(L35-K)") (class "Default")
      (node (ref "L35") (pin "1") (pinfunction "K_1") (pintype "output"))
      (node (ref "L36") (pin "2") (pinfunction "A_2") (pintype "input"))
    )
    (net (code "38") (name "Net-(L36-K)") (class "Default")
      (node (ref "L36") (pin "1") (pinfunction "K_1") (pintype "output"))
      (node (ref "RN3") (pin "6") (pinfunction "2_6") (pintype "passive"))
    )
    (net (code "39") (name "Net-(L37-K)") (class "Default")
      (node (ref "L37") (pin "1") (pinfunction "K_1") (pintype "output"))
      (node (ref "L38") (pin "2") (pinfunction "A_2") (pintype "input"))
    )
    (net (code "40") (name "Net-(L38-K)") (class "Default")
      (node (ref "L38") (pin "1") (pinfunction "K_1") (pintype "output"))
      (node (ref "L39") (pin "2") (pinfunction "A_2") (pintype "input"))
    )
    (net (code "41") (name "Net-(L39-K)") (class "Default")
      (node (ref "L39") (pin "1") (pinfunction "K_1") (pintype "output"))
      (node (ref "RN4") (pin "7") (pinfunction "2_7") (pintype "passive"))
    )
    (net (code "42") (name "Net-(L40-K)") (class "Default")
      (node (ref "L40") (pin "1") (pinfunction "K_1") (pintype "output"))
      (node (ref "L41") (pin "2") (pinfunction "A_2") (pintype "input"))
    )
    (net (code "43") (name "Net-(L41-K)") (class "Default")
      (node (ref "L41") (pin "1") (pinfunction "K_1") (pintype "output"))
      (node (ref "L42") (pin "2") (pinfunction "A_2") (pintype "input"))
    )
    (net (code "44") (name "Net-(L42-K)") (class "Default")
      (node (ref "L42") (pin "1") (pinfunction "K_1") (pintype "output"))
      (node (ref "RN4") (pin "8") (pinfunction "2_8") (pintype "passive"))
    )
    (net (code "45") (name "Net-(L43-K)") (class "Default")
      (node (ref "L43") (pin "1") (pinfunction "K_1") (pintype "output"))
      (node (ref "L44") (pin "2") (pinfunction "A_2") (pintype "input"))
    )
    (net (code "46") (name "Net-(L44-K)") (class "Default")
      (node (ref "L44") (pin "1") (pinfunction "K_1") (pintype "output"))
      (node (ref "L45") (pin "2") (pinfunction "A_2") (pintype "input"))
    )
    (net (code "47") (name "Net-(L45-K)") (class "Default")
      (node (ref "L45") (pin "1") (pinfunction "K_1") (pintype "output"))
      (node (ref "RN4") (pin "5") (pinfunction "2_5") (pintype "passive"))
    )
    (net (code "48") (name "Net-(L46-K)") (class "Default")
      (node (ref "L46") (pin "1") (pinfunction "K_1") (pintype "output"))
      (node (ref "L47") (pin "2") (pinfunction "A_2") (pintype "input"))
    )
    (net (code "49") (name "Net-(L47-K)") (class "Default")
      (node (ref "L47") (pin "1") (pinfunction "K_1") (pintype "output"))
      (node (ref "L48") (pin "2") (pinfunction "A_2") (pintype "input"))
    )
    (net (code "50") (name "Net-(L48-K)") (class "Default")
      (node (ref "L48") (pin "1") (pinfunction "K_1") (pintype "output"))
      (node (ref "RN4") (pin "6") (pinfunction "2_6") (pintype "passive"))
    )
    (net (code "51") (name "Net-(L49-K)") (class "Default")
      (node (ref "L49") (pin "1") (pinfunction "K_1") (pintype "output"))
      (node (ref "L50") (pin "2") (pinfunction "A_2") (pintype "input"))
    )
    (net (code "52") (name "Net-(L50-K)") (class "Default")
      (node (ref "L50") (pin "1") (pinfunction "K_1") (pintype "output"))
      (node (ref "L51") (pin "2") (pinfunction "A_2") (pintype "input"))
    )
    (net (code "53") (name "Net-(L51-K)") (class "Default")
      (node (ref "L51") (pin "1") (pinfunction "K_1") (pintype "output"))
      (node (ref "RN5") (pin "7") (pinfunction "2_7") (pintype "passive"))
    )
    (net (code "54") (name "Net-(L52-K)") (class "Default")
      (node (ref "L52") (pin "1") (pinfunction "K_1") (pintype "output"))
      (node (ref "L53") (pin "2") (pinfunction "A_2") (pintype "input"))
    )
    (net (code "55") (name "Net-(L53-K)") (class "Default")
      (node (ref "L53") (pin "1") (pinfunction "K_1") (pintype "output"))
      (node (ref "L54") (pin "2") (pinfunction "A_2") (pintype "input"))
    )
    (net (code "56") (name "Net-(L54-K)") (class "Default")
      (node (ref "L54") (pin "1") (pinfunction "K_1") (pintype "output"))
      (node (ref "RN5") (pin "8") (pinfunction "2_8") (pintype "passive"))
    )
    (net (code "57") (name "Net-(L55-K)") (class "Default")
      (node (ref "L55") (pin "1") (pinfunction "K_1") (pintype "output"))
      (node (ref "L56") (pin "2") (pinfunction "A_2") (pintype "input"))
    )
    (net (code "58") (name "Net-(L56-K)") (class "Default")
      (node (ref "L56") (pin "1") (pinfunction "K_1") (pintype "output"))
      (node (ref "L57") (pin "2") (pinfunction "A_2") (pintype "input"))
    )
    (net (code "59") (name "Net-(L57-K)") (class "Default")
      (node (ref "L57") (pin "1") (pinfunction "K_1") (pintype "output"))
      (node (ref "RN5") (pin "5") (pinfunction "2_5") (pintype "passive"))
    )
    (net (code "60") (name "Net-(L58-K)") (class "Default")
      (node (ref "L58") (pin "1") (pinfunction "K_1") (pintype "output"))
      (node (ref "L59") (pin "2") (pinfunction "A_2") (pintype "input"))
    )
    (net (code "61") (name "Net-(L59-K)") (class "Default")
      (node (ref "L59") (pin "1") (pinfunction "K_1") (pintype "output"))
      (node (ref "L60") (pin "2") (pinfunction "A_2") (pintype "input"))
    )
    (net (code "62") (name "Net-(L60-K)") (class "Default")
      (node (ref "L60") (pin "1") (pinfunction "K_1") (pintype "output"))
      (node (ref "RN5") (pin "6") (pinfunction "2_6") (pintype "passive"))
    )
    (net (code "63") (name "Net-(L61-K)") (class "Default")
      (node (ref "L61") (pin "1") (pinfunction "K_1") (pintype "output"))
      (node (ref "L62") (pin "2") (pinfunction "A_2") (pintype "input"))
    )
    (net (code "64") (name "Net-(L62-K)") (class "Default")
      (node (ref "L62") (pin "1") (pinfunction "K_1") (pintype "output"))
      (node (ref "L63") (pin "2") (pinfunction "A_2") (pintype "input"))
    )
    (net (code "65") (name "Net-(L63-K)") (class "Default")
      (node (ref "L63") (pin "1") (pinfunction "K_1") (pintype "output"))
      (node (ref "RN6") (pin "7") (pinfunction "2_7") (pintype "passive"))
    )
    (net (code "66") (name "Net-(L64-K)") (class "Default")
      (node (ref "L64") (pin "1") (pinfunction "K_1") (pintype "output"))
      (node (ref "L65") (pin "2") (pinfunction "A_2") (pintype "input"))
    )
    (net (code "67") (name "Net-(L65-K)") (class "Default")
      (node (ref "L65") (pin "1") (pinfunction "K_1") (pintype "output"))
      (node (ref "L66") (pin "2") (pinfunction "A_2") (pintype "input"))
    )
    (net (code "68") (name "Net-(L66-K)") (class "Default")
      (node (ref "L66") (pin "1") (pinfunction "K_1") (pintype "output"))
      (node (ref "RN6") (pin "8") (pinfunction "2_8") (pintype "passive"))
    )
    (net (code "69") (name "Net-(L67-K)") (class "Default")
      (node (ref "L67") (pin "1") (pinfunction "K_1") (pintype "output"))
      (node (ref "L68") (pin "2") (pinfunction "A_2") (pintype "input"))
    )
    (net (code "70") (name "Net-(L68-K)") (class "Default")
      (node (ref "L68") (pin "1") (pinfunction "K_1") (pintype "output"))
      (node (ref "L69") (pin "2") (pinfunction "A_2") (pintype "input"))
    )
    (net (code "71") (name "Net-(L69-K)") (class "Default")
      (node (ref "L69") (pin "1") (pinfunction "K_1") (pintype "output"))
      (node (ref "RN6") (pin "5") (pinfunction "2_5") (pintype "passive"))
    )
    (net (code "72") (name "Net-(L70-K)") (class "Default")
      (node (ref "L70") (pin "1") (pinfunction "K_1") (pintype "output"))
      (node (ref "L71") (pin "2") (pinfunction "A_2") (pintype "input"))
    )
    (net (code "73") (name "Net-(L71-K)") (class "Default")
      (node (ref "L71") (pin "1") (pinfunction "K_1") (pintype "output"))
      (node (ref "L72") (pin "2") (pinfunction "A_2") (pintype "input"))
    )
    (net (code "74") (name "Net-(L72-K)") (class "Default")
      (node (ref "L72") (pin "1") (pinfunction "K_1") (pintype "output"))
      (node (ref "RN6") (pin "6") (pinfunction "2_6") (pintype "passive"))
    )
    (net (code "75") (name "Net-(L73-K)") (class "Default")
      (node (ref "L73") (pin "1") (pinfunction "K_1") (pintype "output"))
      (node (ref "L74") (pin "2") (pinfunction "A_2") (pintype "input"))
    )
    (net (code "76") (name "Net-(L74-K)") (class "Default")
      (node (ref "L74") (pin "1") (pinfunction "K_1") (pintype "output"))
      (node (ref "L75") (pin "2") (pinfunction "A_2") (pintype "input"))
    )
    (net (code "77") (name "Net-(L75-K)") (class "Default")
      (node (ref "L75") (pin "1") (pinfunction "K_1") (pintype "output"))
      (node (ref "RN7") (pin "7") (pinfunction "2_7") (pintype "passive"))
    )
    (net (code "78") (name "Net-(L76-K)") (class "Default")
      (node (ref "L76") (pin "1") (pinfunction "K_1") (pintype "output"))
      (node (ref "L77") (pin "2") (pinfunction "A_2") (pintype "input"))
    )
    (net (code "79") (name "Net-(L77-K)") (class "Default")
      (node (ref "L77") (pin "1") (pinfunction "K_1") (pintype "output"))
      (node (ref "L78") (pin "2") (pinfunction "A_2") (pintype "input"))
    )
    (net (code "80") (name "Net-(L78-K)") (class "Default")
      (node (ref "L78") (pin "1") (pinfunction "K_1") (pintype "output"))
      (node (ref "RN7") (pin "8") (pinfunction "2_8") (pintype "passive"))
    )
    (net (code "81") (name "Net-(L79-K)") (class "Default")
      (node (ref "L79") (pin "1") (pinfunction "K_1") (pintype "output"))
      (node (ref "L80") (pin "2") (pinfunction "A_2") (pintype "input"))
    )
    (net (code "82") (name "Net-(L80-K)") (class "Default")
      (node (ref "L80") (pin "1") (pinfunction "K_1") (pintype "output"))
      (node (ref "L81") (pin "2") (pinfunction "A_2") (pintype "input"))
    )
    (net (code "83") (name "Net-(L81-K)") (class "Default")
      (node (ref "L81") (pin "1") (pinfunction "K_1") (pintype "output"))
      (node (ref "RN7") (pin "5") (pinfunction "2_5") (pintype "passive"))
    )
    (net (code "84") (name "Net-(L82-K)") (class "Default")
      (node (ref "L82") (pin "1") (pinfunction "K_1") (pintype "output"))
      (node (ref "L83") (pin "2") (pinfunction "A_2") (pintype "input"))
    )
    (net (code "85") (name "Net-(L83-K)") (class "Default")
      (node (ref "L83") (pin "1") (pinfunction "K_1") (pintype "output"))
      (node (ref "L84") (pin "2") (pinfunction "A_2") (pintype "input"))
    )
    (net (code "86") (name "Net-(L84-K)") (class "Default")
      (node (ref "L84") (pin "1") (pinfunction "K_1") (pintype "output"))
      (node (ref "RN7") (pin "6") (pinfunction "2_6") (pintype "passive"))
    )
    (net (code "87") (name "Net-(L85-K)") (class "Default")
      (node (ref "L85") (pin "1") (pinfunction "K_1") (pintype "output"))
      (node (ref "L86") (pin "2") (pinfunction "A_2") (pintype "input"))
    )
    (net (code "88") (name "Net-(L86-K)") (class "Default")
      (node (ref "L86") (pin "1") (pinfunction "K_1") (pintype "output"))
      (node (ref "L87") (pin "2") (pinfunction "A_2") (pintype "input"))
    )
    (net (code "89") (name "Net-(L87-K)") (class "Default")
      (node (ref "L87") (pin "1") (pinfunction "K_1") (pintype "output"))
      (node (ref "RN8") (pin "7") (pinfunction "2_7") (pintype "passive"))
    )
    (net (code "90") (name "Net-(L88-K)") (class "Default")
      (node (ref "L88") (pin "1") (pinfunction "K_1") (pintype "output"))
      (node (ref "L89") (pin "2") (pinfunction "A_2") (pintype "input"))
    )
    (net (code "91") (name "Net-(L89-K)") (class "Default")
      (node (ref "L89") (pin "1") (pinfunction "K_1") (pintype "output"))
      (node (ref "L90") (pin "2") (pinfunction "A_2") (pintype "input"))
    )
    (net (code "92") (name "Net-(L90-K)") (class "Default")
      (node (ref "L90") (pin "1") (pinfunction "K_1") (pintype "output"))
      (node (ref "RN8") (pin "8") (pinfunction "2_8") (pintype "passive"))
    )
    (net (code "93") (name "Net-(L91-K)") (class "Default")
      (node (ref "L91") (pin "1") (pinfunction "K_1") (pintype "output"))
      (node (ref "L92") (pin "2") (pinfunction "A_2") (pintype "input"))
    )
    (net (code "94") (name "Net-(L92-K)") (class "Default")
      (node (ref "L92") (pin "1") (pinfunction "K_1") (pintype "output"))
      (node (ref "L93") (pin "2") (pinfunction "A_2") (pintype "input"))
    )
    (net (code "95") (name "Net-(L93-K)") (class "Default")
      (node (ref "L93") (pin "1") (pinfunction "K_1") (pintype "output"))
      (node (ref "RN8") (pin "5") (pinfunction "2_5") (pintype "passive"))
    )
    (net (code "96") (name "Net-(L94-K)") (class "Default")
      (node (ref "L94") (pin "1") (pinfunction "K_1") (pintype "output"))
      (node (ref "L95") (pin "2") (pinfunction "A_2") (pintype "input"))
    )
    (net (code "97") (name "Net-(L95-K)") (class "Default")
      (node (ref "L95") (pin "1") (pinfunction "K_1") (pintype "output"))
      (node (ref "L96") (pin "2") (pinfunction "A_2") (pintype "input"))
    )
    (net (code "98") (name "Net-(L96-K)") (class "Default")
      (node (ref "L96") (pin "1") (pinfunction "K_1") (pintype "output"))
      (node (ref "RN8") (pin "6") (pinfunction "2_6") (pintype "passive"))
    )
  )
)
